# Un_51_V1_1.net
KiCad netlist of a schematic drawn in EAGLE
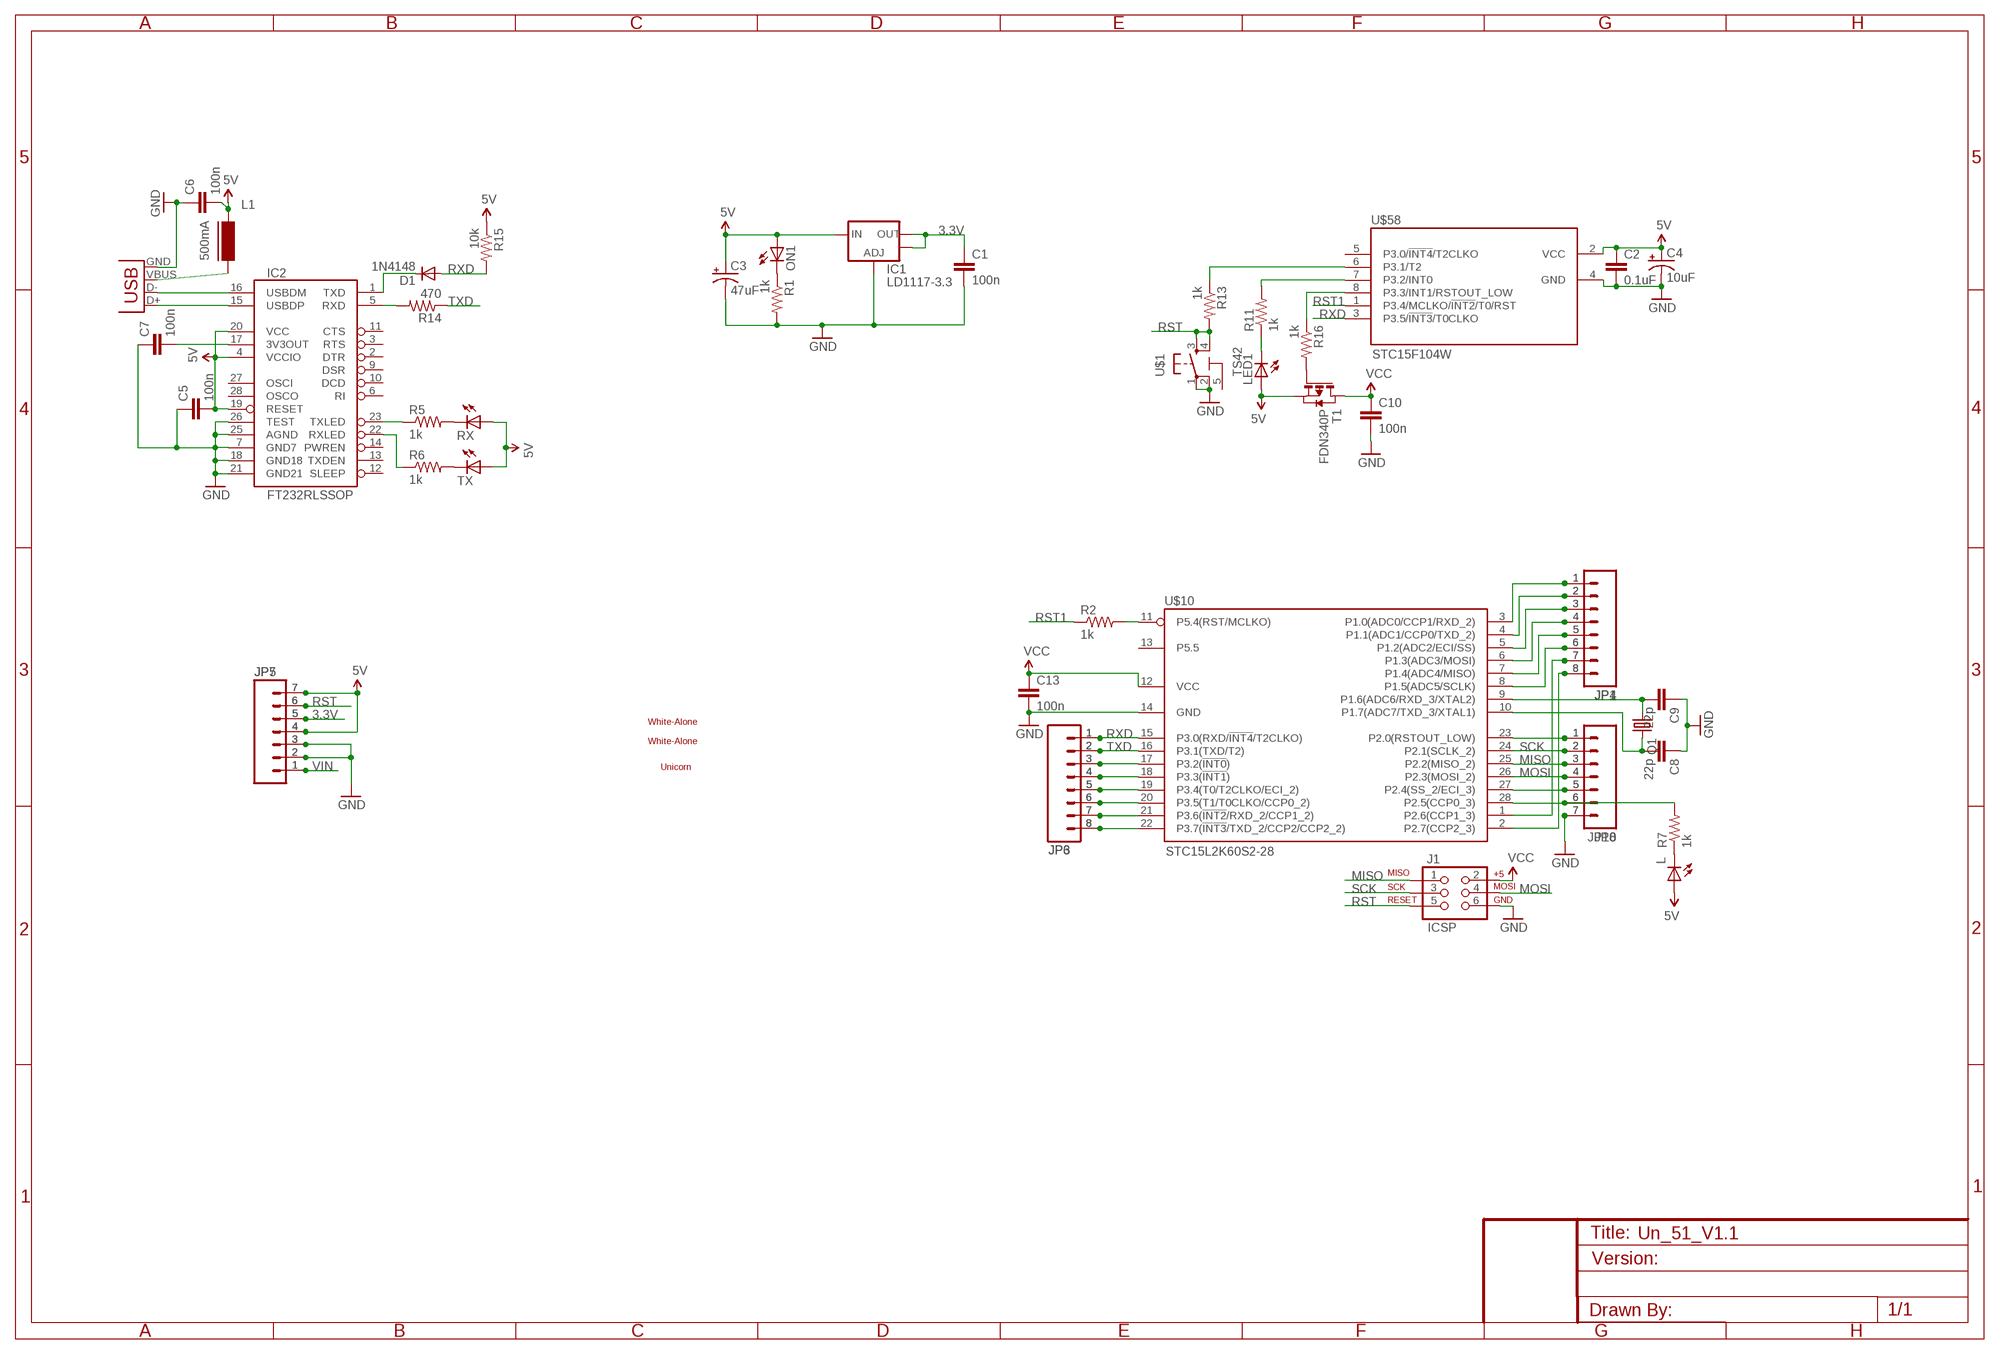
[diagram p0: schematic, sheet 1]

(export (version "E")
  (design (tool "Eeschema 10.0.6"))
  (components
    (comp (ref "C1")
      (value "100n")
      (footprint "eagle-import:0603-CAP")
      (libsource (lib "eagle-import") (part "2SparkFun_CAP0603-CAP"))
    )
    (comp (ref "C2")
      (value "0.1uF")
      (footprint "eagle-import:0603-CAP")
      (libsource (lib "eagle-import") (part "2SparkFun_CAP0603-CAP"))
    )
    (comp (ref "C3")
      (value "47uF")
      (footprint "eagle-import:PANASONIC_D")
      (libsource (lib "eagle-import") (part "CAP_POLD"))
    )
    (comp (ref "C4")
      (value "10uF")
      (footprint "eagle-import:EIA3216")
      (libsource (lib "eagle-import") (part "CAP_POL1206"))
    )
    (comp (ref "C5")
      (value "100n")
      (footprint "eagle-import:0603-CAP")
      (libsource (lib "eagle-import") (part "2SparkFun_CAP0603-CAP"))
    )
    (comp (ref "C6")
      (value "100n")
      (footprint "eagle-import:0603-CAP")
      (libsource (lib "eagle-import") (part "2SparkFun_CAP0603-CAP"))
    )
    (comp (ref "C7")
      (value "100n")
      (footprint "eagle-import:0603-CAP")
      (libsource (lib "eagle-import") (part "2SparkFun_CAP0603-CAP"))
    )
    (comp (ref "C8")
      (value "22p")
      (footprint "eagle-import:0603-CAP")
      (libsource (lib "eagle-import") (part "2SparkFun_CAP0603-CAP"))
    )
    (comp (ref "C9")
      (value "22p")
      (footprint "eagle-import:0603-CAP")
      (libsource (lib "eagle-import") (part "2SparkFun_CAP0603-CAP"))
    )
    (comp (ref "C10")
      (value "100n")
      (footprint "eagle-import:0603-CAP")
      (libsource (lib "eagle-import") (part "2SparkFun_CAP0603-CAP"))
    )
    (comp (ref "C13")
      (value "100n")
      (footprint "eagle-import:0603-CAP")
      (libsource (lib "eagle-import") (part "CAP0603-CAP"))
    )
    (comp (ref "D1")
      (value "1N4148")
      (footprint "eagle-import:SOD-323")
      (libsource (lib "eagle-import") (part "DIODESOD"))
    )
    (comp (ref "IC1")
      (value "LD1117-3.3")
      (footprint "eagle-import:SOT223")
      (libsource (lib "eagle-import") (part "V_REG_LM1117SOT223"))
    )
    (comp (ref "IC2")
      (value "FT232RLSSOP")
      (footprint "eagle-import:SSOP28DB")
      (libsource (lib "eagle-import") (part "FT232RLSSOP"))
    )
    (comp (ref "J1")
      (value "ICSP")
      (footprint "eagle-import:2X3")
      (libsource (lib "eagle-import") (part "AVR_SPI_PRG_6PTH"))
    )
    (comp (ref "JP1")
      (value "M081X08")
      (footprint "eagle-import:1X08")
      (libsource (lib "eagle-import") (part "M081X08"))
    )
    (comp (ref "JP3")
      (value "M08")
      (footprint "eagle-import:1X08")
      (libsource (lib "eagle-import") (part "M08"))
    )
    (comp (ref "JP4")
      (value "M081X08")
      (footprint "eagle-import:1X08")
      (libsource (lib "eagle-import") (part "M081X08"))
    )
    (comp (ref "JP5")
      (value "M07")
      (footprint "eagle-import:1X07")
      (libsource (lib "eagle-import") (part "M07"))
    )
    (comp (ref "JP6")
      (value "M08")
      (footprint "eagle-import:1X08")
      (libsource (lib "eagle-import") (part "M08"))
    )
    (comp (ref "JP7")
      (value "M07")
      (footprint "eagle-import:1X07")
      (libsource (lib "eagle-import") (part "M07"))
    )
    (comp (ref "JP8")
      (value "M07")
      (footprint "eagle-import:1X07")
      (libsource (lib "eagle-import") (part "M07"))
    )
    (comp (ref "JP10")
      (value "M07")
      (footprint "eagle-import:1X07")
      (libsource (lib "eagle-import") (part "M07"))
    )
    (comp (ref "L")
      (value "LED0805")
      (footprint "eagle-import:LED-0805")
      (libsource (lib "eagle-import") (part "LED0805"))
    )
    (comp (ref "L1")
      (value "500mA")
      (footprint "eagle-import:FB805")
      (libsource (lib "eagle-import") (part "FERRITE-0805"))
    )
    (comp (ref "LED1")
      (value "LED0805")
      (footprint "eagle-import:LED-0805")
      (libsource (lib "eagle-import") (part "2SparkFun_LED0805"))
    )
    (comp (ref "ON1")
      (value "LED0805")
      (footprint "eagle-import:LED-0805")
      (libsource (lib "eagle-import") (part "LED0805"))
    )
    (comp (ref "Q1")
      (value "CRYSTALHC49US")
      (footprint "eagle-import:HC49US")
      (libsource (lib "eagle-import") (part "CRYSTALHC49US"))
    )
    (comp (ref "R1")
      (value "1k")
      (footprint "eagle-import:0603-RES")
      (libsource (lib "eagle-import") (part "RESISTOR0603-RES"))
    )
    (comp (ref "R2")
      (value "1k")
      (footprint "eagle-import:0603-RES")
      (libsource (lib "eagle-import") (part "RESISTOR0603-RES"))
    )
    (comp (ref "R5")
      (value "1k")
      (footprint "eagle-import:0603-RES")
      (libsource (lib "eagle-import") (part "RESISTOR0603-RES"))
    )
    (comp (ref "R6")
      (value "1k")
      (footprint "eagle-import:0603-RES")
      (libsource (lib "eagle-import") (part "RESISTOR0603-RES"))
    )
    (comp (ref "R7")
      (value "1k")
      (footprint "eagle-import:0603-RES")
      (libsource (lib "eagle-import") (part "RESISTOR0603-RES"))
    )
    (comp (ref "R11")
      (value "1k")
      (footprint "eagle-import:0603-RES")
      (libsource (lib "eagle-import") (part "RESISTOR0603-RES"))
    )
    (comp (ref "R13")
      (value "1k")
      (footprint "eagle-import:0603-RES")
      (libsource (lib "eagle-import") (part "RESISTOR0603-RES"))
    )
    (comp (ref "R14")
      (value "470")
      (footprint "eagle-import:0603-RES")
      (libsource (lib "eagle-import") (part "RESISTOR0603-RES"))
    )
    (comp (ref "R15")
      (value "10k")
      (footprint "eagle-import:0603-RES")
      (libsource (lib "eagle-import") (part "RESISTOR0603-RES"))
    )
    (comp (ref "R16")
      (value "1k")
      (footprint "eagle-import:0603-RES")
      (libsource (lib "eagle-import") (part "RESISTOR0603-RES"))
    )
    (comp (ref "RX")
      (value "LED0805")
      (footprint "eagle-import:LED-0805")
      (libsource (lib "eagle-import") (part "LED0805"))
    )
    (comp (ref "T1")
      (value "FDN340P")
      (footprint "eagle-import:SOT-23")
      (libsource (lib "eagle-import") (part "PMOSSOT23"))
    )
    (comp (ref "TX")
      (value "LED0805")
      (footprint "eagle-import:LED-0805")
      (libsource (lib "eagle-import") (part "LED0805"))
    )
    (comp (ref "U$1")
      (value "TS42")
      (footprint "eagle-import:TS42")
      (libsource (lib "eagle-import") (part "TS42"))
    )
    (comp (ref "U$3")
      (value "UNICORN")
      (footprint "eagle-import:UNICORN_1")
      (libsource (lib "eagle-import") (part "UNICORN"))
    )
    (comp (ref "U$7")
      (value "WHITE-ALONE_0")
      (footprint "eagle-import:WHITE-ALONE_0")
      (libsource (lib "eagle-import") (part "WHITE-ALONE_0"))
    )
    (comp (ref "U$10")
      (value "STC15L2K60S2-28")
      (footprint "eagle-import:SO-28W")
      (libsource (lib "eagle-import") (part "STC15L2K60S2-28"))
    )
    (comp (ref "U$11")
      (value "WHITE-ALONE_0")
      (footprint "eagle-import:WHITE-ALONE_0")
      (libsource (lib "eagle-import") (part "WHITE-ALONE_0"))
    )
    (comp (ref "U$58")
      (value "STC15F104W")
      (footprint "eagle-import:SO08")
      (libsource (lib "eagle-import") (part "STC15F104W"))
    )
    (comp (ref "X1")
      (value "USBSMD")
      (footprint "eagle-import:USB-MINIB")
      (libsource (lib "eagle-import") (part "USBSMD"))
    )
  )
  (nets
    (net (code "1") (name "/3.3V") (class "Default")
      (node (ref "C1") (pin "1") (pinfunction "1_1") (pintype "passive"))
      (node (ref "IC1") (pin "2") (pinfunction "OUT_2") (pintype "output"))
      (node (ref "IC1") (pin "4") (pinfunction "OUT_4") (pintype "output"))
      (node (ref "JP5") (pin "5") (pinfunction "5_5") (pintype "passive"))
      (node (ref "JP7") (pin "5") (pinfunction "5_5") (pintype "passive"))
    )
    (net (code "2") (name "/MISO") (class "Default")
      (node (ref "J1") (pin "1") (pinfunction "1_1") (pintype "passive"))
      (node (ref "JP10") (pin "3") (pinfunction "3_3") (pintype "passive"))
      (node (ref "JP8") (pin "3") (pinfunction "3_3") (pintype "passive"))
      (node (ref "U$10") (pin "25") (pinfunction "P2.2(MISO_2)_25") (pintype "bidirectional"))
    )
    (net (code "3") (name "/MOSI") (class "Default")
      (node (ref "J1") (pin "4") (pinfunction "4_4") (pintype "passive"))
      (node (ref "JP10") (pin "4") (pinfunction "4_4") (pintype "passive"))
      (node (ref "JP8") (pin "4") (pinfunction "4_4") (pintype "passive"))
      (node (ref "U$10") (pin "26") (pinfunction "P2.3(MOSI_2)_26") (pintype "bidirectional"))
    )
    (net (code "4") (name "/RST") (class "Default")
      (node (ref "J1") (pin "5") (pinfunction "5_5") (pintype "passive"))
      (node (ref "JP5") (pin "6") (pinfunction "6_6") (pintype "passive"))
      (node (ref "JP7") (pin "6") (pinfunction "6_6") (pintype "passive"))
      (node (ref "R13") (pin "2") (pinfunction "2_2") (pintype "passive"))
      (node (ref "U$1") (pin "3") (pinfunction "3_3") (pintype "passive"))
      (node (ref "U$1") (pin "4") (pinfunction "4_4") (pintype "passive"))
    )
    (net (code "5") (name "/RST1") (class "Default")
      (node (ref "R2") (pin "1") (pinfunction "1_1") (pintype "passive"))
      (node (ref "U$58") (pin "1") (pinfunction "P3.4/MCLKO/~{INT2}/T0/RST_1") (pintype "bidirectional"))
    )
    (net (code "6") (name "/RXD") (class "Default")
      (node (ref "D1") (pin "2") (pinfunction "A_2") (pintype "passive"))
      (node (ref "JP3") (pin "1") (pinfunction "1_1") (pintype "passive"))
      (node (ref "JP6") (pin "1") (pinfunction "1_1") (pintype "passive"))
      (node (ref "R15") (pin "2") (pinfunction "2_2") (pintype "passive"))
      (node (ref "U$10") (pin "15") (pinfunction "P3.0(RXD/~{INT4}/T2CLKO)_15") (pintype "bidirectional"))
      (node (ref "U$58") (pin "3") (pinfunction "P3.5/~{INT3}/T0CLKO_3") (pintype "bidirectional"))
    )
    (net (code "7") (name "/SCK") (class "Default")
      (node (ref "J1") (pin "3") (pinfunction "3_3") (pintype "passive"))
      (node (ref "JP10") (pin "2") (pinfunction "2_2") (pintype "passive"))
      (node (ref "JP8") (pin "2") (pinfunction "2_2") (pintype "passive"))
      (node (ref "U$10") (pin "24") (pinfunction "P2.1(SCLK_2)_24") (pintype "bidirectional"))
    )
    (net (code "8") (name "/TXD") (class "Default")
      (node (ref "JP3") (pin "2") (pinfunction "2_2") (pintype "passive"))
      (node (ref "JP6") (pin "2") (pinfunction "2_2") (pintype "passive"))
      (node (ref "R14") (pin "1") (pinfunction "1_1") (pintype "passive"))
      (node (ref "U$10") (pin "16") (pinfunction "P3.1(TXD/T2)_16") (pintype "bidirectional"))
    )
    (net (code "9") (name "/VIN") (class "Default")
      (node (ref "JP5") (pin "1") (pinfunction "1_1") (pintype "passive"))
      (node (ref "JP7") (pin "1") (pinfunction "1_1") (pintype "passive"))
    )
    (net (code "10") (name "5V") (class "Default")
      (node (ref "C2") (pin "1") (pinfunction "1_1") (pintype "passive"))
      (node (ref "C3") (pin "+") (pinfunction "+_+") (pintype "passive"))
      (node (ref "C4") (pin "A") (pinfunction "+_A") (pintype "passive"))
      (node (ref "C5") (pin "2") (pinfunction "2_2") (pintype "passive"))
      (node (ref "C6") (pin "2") (pinfunction "2_2") (pintype "passive"))
      (node (ref "IC1") (pin "3") (pinfunction "IN_3") (pintype "input"))
      (node (ref "IC2") (pin "19") (pinfunction "RESET_19") (pintype "input"))
      (node (ref "IC2") (pin "20") (pinfunction "VCC_20") (pintype "power_in"))
      (node (ref "IC2") (pin "4") (pinfunction "VCCIO_4") (pintype "power_in"))
      (node (ref "JP5") (pin "4") (pinfunction "4_4") (pintype "passive"))
      (node (ref "JP5") (pin "7") (pinfunction "7_7") (pintype "passive"))
      (node (ref "JP7") (pin "4") (pinfunction "4_4") (pintype "passive"))
      (node (ref "JP7") (pin "7") (pinfunction "7_7") (pintype "passive"))
      (node (ref "L") (pin "1") (pinfunction "A_1") (pintype "passive"))
      (node (ref "L1") (pin "1") (pinfunction "1_1") (pintype "passive"))
      (node (ref "LED1") (pin "1") (pinfunction "A_1") (pintype "passive"))
      (node (ref "ON1") (pin "1") (pinfunction "A_1") (pintype "passive"))
      (node (ref "R15") (pin "1") (pinfunction "1_1") (pintype "passive"))
      (node (ref "RX") (pin "1") (pinfunction "A_1") (pintype "passive"))
      (node (ref "T1") (pin "2") (pinfunction "S_2") (pintype "passive"))
      (node (ref "TX") (pin "1") (pinfunction "A_1") (pintype "passive"))
      (node (ref "U$58") (pin "2") (pinfunction "VCC_2") (pintype "bidirectional"))
    )
    (net (code "11") (name "GND") (class "Default")
      (node (ref "C1") (pin "2") (pinfunction "2_2") (pintype "passive"))
      (node (ref "C10") (pin "2") (pinfunction "2_2") (pintype "passive"))
      (node (ref "C13") (pin "2") (pinfunction "2_2") (pintype "passive"))
      (node (ref "C2") (pin "2") (pinfunction "2_2") (pintype "passive"))
      (node (ref "C3") (pin "-") (pinfunction "-_-") (pintype "passive"))
      (node (ref "C4") (pin "C") (pinfunction "-_C") (pintype "passive"))
      (node (ref "C5") (pin "1") (pinfunction "1_1") (pintype "passive"))
      (node (ref "C6") (pin "1") (pinfunction "1_1") (pintype "passive"))
      (node (ref "C7") (pin "1") (pinfunction "1_1") (pintype "passive"))
      (node (ref "C8") (pin "1") (pinfunction "1_1") (pintype "passive"))
      (node (ref "C9") (pin "1") (pinfunction "1_1") (pintype "passive"))
      (node (ref "IC1") (pin "1") (pinfunction "ADJ_1") (pintype "input"))
      (node (ref "IC2") (pin "18") (pinfunction "GND18_18") (pintype "power_in"))
      (node (ref "IC2") (pin "21") (pinfunction "GND21_21") (pintype "power_in"))
      (node (ref "IC2") (pin "25") (pinfunction "AGND_25") (pintype "power_in"))
      (node (ref "IC2") (pin "26") (pinfunction "TEST_26") (pintype "input"))
      (node (ref "IC2") (pin "7") (pinfunction "GND7_7") (pintype "power_in"))
      (node (ref "J1") (pin "6") (pinfunction "6_6") (pintype "passive"))
      (node (ref "JP10") (pin "7") (pinfunction "7_7") (pintype "passive"))
      (node (ref "JP5") (pin "2") (pinfunction "2_2") (pintype "passive"))
      (node (ref "JP5") (pin "3") (pinfunction "3_3") (pintype "passive"))
      (node (ref "JP7") (pin "2") (pinfunction "2_2") (pintype "passive"))
      (node (ref "JP7") (pin "3") (pinfunction "3_3") (pintype "passive"))
      (node (ref "JP8") (pin "7") (pinfunction "7_7") (pintype "passive"))
      (node (ref "R1") (pin "2") (pinfunction "2_2") (pintype "passive"))
      (node (ref "U$1") (pin "1") (pinfunction "1_1") (pintype "passive"))
      (node (ref "U$1") (pin "2") (pinfunction "2_2") (pintype "passive"))
      (node (ref "U$10") (pin "14") (pinfunction "GND_14") (pintype "bidirectional"))
      (node (ref "U$58") (pin "4") (pinfunction "GND_4") (pintype "bidirectional"))
      (node (ref "X1") (pin "GND") (pinfunction "GND_GND") (pintype "bidirectional"))
    )
    (net (code "12") (name "Net-(D1-C)") (class "Default")
      (node (ref "D1") (pin "1") (pinfunction "C_1") (pintype "passive"))
      (node (ref "IC2") (pin "1") (pinfunction "TXD_1") (pintype "output"))
    )
    (net (code "13") (name "Net-(IC2-3V3OUT)") (class "Default")
      (node (ref "C7") (pin "2") (pinfunction "2_2") (pintype "passive"))
      (node (ref "IC2") (pin "17") (pinfunction "3V3OUT_17") (pintype "output"))
    )
    (net (code "14") (name "Net-(IC2-RXD)") (class "Default")
      (node (ref "IC2") (pin "5") (pinfunction "RXD_5") (pintype "input"))
      (node (ref "R14") (pin "2") (pinfunction "2_2") (pintype "passive"))
    )
    (net (code "15") (name "Net-(IC2-RXLED)") (class "Default")
      (node (ref "IC2") (pin "22") (pinfunction "RXLED_22") (pintype "input"))
      (node (ref "R6") (pin "1") (pinfunction "1_1") (pintype "passive"))
    )
    (net (code "16") (name "Net-(IC2-TXLED)") (class "Default")
      (node (ref "IC2") (pin "23") (pinfunction "TXLED_23") (pintype "input"))
      (node (ref "R5") (pin "1") (pinfunction "1_1") (pintype "passive"))
    )
    (net (code "17") (name "Net-(IC2-USBDM)") (class "Default")
      (node (ref "IC2") (pin "16") (pinfunction "USBDM_16") (pintype "bidirectional"))
      (node (ref "X1") (pin "D-") (pinfunction "D-_D-") (pintype "bidirectional"))
    )
    (net (code "18") (name "Net-(IC2-USBDP)") (class "Default")
      (node (ref "IC2") (pin "15") (pinfunction "USBDP_15") (pintype "bidirectional"))
      (node (ref "X1") (pin "D+") (pinfunction "D+_D+") (pintype "bidirectional"))
    )
    (net (code "19") (name "Net-(L-C)") (class "Default")
      (node (ref "L") (pin "2") (pinfunction "C_2") (pintype "passive"))
      (node (ref "R7") (pin "1") (pinfunction "1_1") (pintype "passive"))
    )
    (net (code "20") (name "Net-(L1-Pad2)") (class "Default")
      (node (ref "L1") (pin "2") (pinfunction "2_2") (pintype "passive"))
      (node (ref "X1") (pin "VBUS") (pinfunction "VBUS_VBUS") (pintype "bidirectional"))
    )
    (net (code "21") (name "Net-(LED1-C)") (class "Default")
      (node (ref "LED1") (pin "2") (pinfunction "C_2") (pintype "passive"))
      (node (ref "R11") (pin "1") (pinfunction "1_1") (pintype "passive"))
    )
    (net (code "22") (name "Net-(ON1-C)") (class "Default")
      (node (ref "ON1") (pin "2") (pinfunction "C_2") (pintype "passive"))
      (node (ref "R1") (pin "1") (pinfunction "1_1") (pintype "passive"))
    )
    (net (code "23") (name "Net-(RX-C)") (class "Default")
      (node (ref "R5") (pin "2") (pinfunction "2_2") (pintype "passive"))
      (node (ref "RX") (pin "2") (pinfunction "C_2") (pintype "passive"))
    )
    (net (code "24") (name "Net-(T1-G)") (class "Default")
      (node (ref "R16") (pin "2") (pinfunction "2_2") (pintype "passive"))
      (node (ref "T1") (pin "3") (pinfunction "G_3") (pintype "passive"))
    )
    (net (code "25") (name "Net-(TX-C)") (class "Default")
      (node (ref "R6") (pin "2") (pinfunction "2_2") (pintype "passive"))
      (node (ref "TX") (pin "2") (pinfunction "C_2") (pintype "passive"))
    )
    (net (code "26") (name "Net-(U$10-P1.0(ADC0{slash}CCP1{slash}RXD_2))") (class "Default")
      (node (ref "JP1") (pin "1") (pinfunction "1_1") (pintype "passive"))
      (node (ref "JP4") (pin "1") (pinfunction "1_1") (pintype "passive"))
      (node (ref "U$10") (pin "3") (pinfunction "P1.0(ADC0/CCP1/RXD_2)_3") (pintype "bidirectional"))
    )
    (net (code "27") (name "Net-(U$10-P1.1(ADC1{slash}CCP0{slash}TXD_2))") (class "Default")
      (node (ref "JP1") (pin "2") (pinfunction "2_2") (pintype "passive"))
      (node (ref "JP4") (pin "2") (pinfunction "2_2") (pintype "passive"))
      (node (ref "U$10") (pin "4") (pinfunction "P1.1(ADC1/CCP0/TXD_2)_4") (pintype "bidirectional"))
    )
    (net (code "28") (name "Net-(U$10-P1.2(ADC2{slash}ECI{slash}SS))") (class "Default")
      (node (ref "JP1") (pin "3") (pinfunction "3_3") (pintype "passive"))
      (node (ref "JP4") (pin "3") (pinfunction "3_3") (pintype "passive"))
      (node (ref "U$10") (pin "5") (pinfunction "P1.2(ADC2/ECI/SS)_5") (pintype "bidirectional"))
    )
    (net (code "29") (name "Net-(U$10-P1.3(ADC3{slash}MOSI))") (class "Default")
      (node (ref "JP1") (pin "4") (pinfunction "4_4") (pintype "passive"))
      (node (ref "JP4") (pin "4") (pinfunction "4_4") (pintype "passive"))
      (node (ref "U$10") (pin "6") (pinfunction "P1.3(ADC3/MOSI)_6") (pintype "bidirectional"))
    )
    (net (code "30") (name "Net-(U$10-P1.4(ADC4{slash}MISO))") (class "Default")
      (node (ref "JP1") (pin "5") (pinfunction "5_5") (pintype "passive"))
      (node (ref "JP4") (pin "5") (pinfunction "5_5") (pintype "passive"))
      (node (ref "U$10") (pin "7") (pinfunction "P1.4(ADC4/MISO)_7") (pintype "bidirectional"))
    )
    (net (code "31") (name "Net-(U$10-P1.5(ADC5{slash}SCLK))") (class "Default")
      (node (ref "JP1") (pin "6") (pinfunction "6_6") (pintype "passive"))
      (node (ref "JP4") (pin "6") (pinfunction "6_6") (pintype "passive"))
      (node (ref "U$10") (pin "8") (pinfunction "P1.5(ADC5/SCLK)_8") (pintype "bidirectional"))
    )
    (net (code "32") (name "Net-(U$10-P1.6(ADC6{slash}RXD_3{slash}XTAL2))") (class "Default")
      (node (ref "C9") (pin "2") (pinfunction "2_2") (pintype "passive"))
      (node (ref "Q1") (pin "1") (pinfunction "1_1") (pintype "passive"))
      (node (ref "U$10") (pin "9") (pinfunction "P1.6(ADC6/RXD_3/XTAL2)_9") (pintype "bidirectional"))
    )
    (net (code "33") (name "Net-(U$10-P1.7(ADC7{slash}TXD_3{slash}XTAL1))") (class "Default")
      (node (ref "C8") (pin "2") (pinfunction "2_2") (pintype "passive"))
      (node (ref "Q1") (pin "2") (pinfunction "2_2") (pintype "passive"))
      (node (ref "U$10") (pin "10") (pinfunction "P1.7(ADC7/TXD_3/XTAL1)_10") (pintype "bidirectional"))
    )
    (net (code "34") (name "Net-(U$10-P2.0(RSTOUT_LOW))") (class "Default")
      (node (ref "JP10") (pin "1") (pinfunction "1_1") (pintype "passive"))
      (node (ref "JP8") (pin "1") (pinfunction "1_1") (pintype "passive"))
      (node (ref "U$10") (pin "23") (pinfunction "P2.0(RSTOUT_LOW)_23") (pintype "bidirectional"))
    )
    (net (code "35") (name "Net-(U$10-P2.4(SS_2{slash}ECI_3))") (class "Default")
      (node (ref "JP10") (pin "5") (pinfunction "5_5") (pintype "passive"))
      (node (ref "JP8") (pin "5") (pinfunction "5_5") (pintype "passive"))
      (node (ref "U$10") (pin "27") (pinfunction "P2.4(SS_2/ECI_3)_27") (pintype "bidirectional"))
    )
    (net (code "36") (name "Net-(U$10-P2.5(CCP0_3))") (class "Default")
      (node (ref "JP10") (pin "6") (pinfunction "6_6") (pintype "passive"))
      (node (ref "JP8") (pin "6") (pinfunction "6_6") (pintype "passive"))
      (node (ref "R7") (pin "2") (pinfunction "2_2") (pintype "passive"))
      (node (ref "U$10") (pin "28") (pinfunction "P2.5(CCP0_3)_28") (pintype "bidirectional"))
    )
    (net (code "37") (name "Net-(U$10-P2.6(CCP1_3))") (class "Default")
      (node (ref "JP1") (pin "7") (pinfunction "7_7") (pintype "passive"))
      (node (ref "JP4") (pin "7") (pinfunction "7_7") (pintype "passive"))
      (node (ref "U$10") (pin "1") (pinfunction "P2.6(CCP1_3)_1") (pintype "bidirectional"))
    )
    (net (code "38") (name "Net-(U$10-P2.7(CCP2_3))") (class "Default")
      (node (ref "JP1") (pin "8") (pinfunction "8_8") (pintype "passive"))
      (node (ref "JP4") (pin "8") (pinfunction "8_8") (pintype "passive"))
      (node (ref "U$10") (pin "2") (pinfunction "P2.7(CCP2_3)_2") (pintype "bidirectional"))
    )
    (net (code "39") (name "Net-(U$10-P3.2(~{INT0}))") (class "Default")
      (node (ref "JP3") (pin "3") (pinfunction "3_3") (pintype "passive"))
      (node (ref "JP6") (pin "3") (pinfunction "3_3") (pintype "passive"))
      (node (ref "U$10") (pin "17") (pinfunction "P3.2(~{INT0})_17") (pintype "bidirectional"))
    )
    (net (code "40") (name "Net-(U$10-P3.3(~{INT1}))") (class "Default")
      (node (ref "JP3") (pin "4") (pinfunction "4_4") (pintype "passive"))
      (node (ref "JP6") (pin "4") (pinfunction "4_4") (pintype "passive"))
      (node (ref "U$10") (pin "18") (pinfunction "P3.3(~{INT1})_18") (pintype "bidirectional"))
    )
    (net (code "41") (name "Net-(U$10-P3.4(T0{slash}T2CLKO{slash}ECI_2))") (class "Default")
      (node (ref "JP3") (pin "5") (pinfunction "5_5") (pintype "passive"))
      (node (ref "JP6") (pin "5") (pinfunction "5_5") (pintype "passive"))
      (node (ref "U$10") (pin "19") (pinfunction "P3.4(T0/T2CLKO/ECI_2)_19") (pintype "bidirectional"))
    )
    (net (code "42") (name "Net-(U$10-P3.5(T1{slash}T0CLKO{slash}CCP0_2))") (class "Default")
      (node (ref "JP3") (pin "6") (pinfunction "6_6") (pintype "passive"))
      (node (ref "JP6") (pin "6") (pinfunction "6_6") (pintype "passive"))
      (node (ref "U$10") (pin "20") (pinfunction "P3.5(T1/T0CLKO/CCP0_2)_20") (pintype "bidirectional"))
    )
    (net (code "43") (name "Net-(U$10-P3.6(~{INT2}{slash}RXD_2{slash}CCP1_2))") (class "Default")
      (node (ref "JP3") (pin "7") (pinfunction "7_7") (pintype "passive"))
      (node (ref "JP6") (pin "7") (pinfunction "7_7") (pintype "passive"))
      (node (ref "U$10") (pin "21") (pinfunction "P3.6(~{INT2}/RXD_2/CCP1_2)_21") (pintype "bidirectional"))
    )
    (net (code "44") (name "Net-(U$10-P3.7(~{INT3}{slash}TXD_2{slash}CCP2{slash}CCP2_2))") (class "Default")
      (node (ref "JP3") (pin "8") (pinfunction "8_8") (pintype "passive"))
      (node (ref "JP6") (pin "8") (pinfunction "8_8") (pintype "passive"))
      (node (ref "U$10") (pin "22") (pinfunction "P3.7(~{INT3}/TXD_2/CCP2/CCP2_2)_22") (pintype "bidirectional"))
    )
    (net (code "45") (name "Net-(U$10-P5.4(RST{slash}MCLKO))") (class "Default")
      (node (ref "R2") (pin "2") (pinfunction "2_2") (pintype "passive"))
      (node (ref "U$10") (pin "11") (pinfunction "P5.4(RST/MCLKO)_11") (pintype "bidirectional"))
    )
    (net (code "46") (name "Net-(U$58-P3.1{slash}T2)") (class "Default")
      (node (ref "R13") (pin "1") (pinfunction "1_1") (pintype "passive"))
      (node (ref "U$58") (pin "6") (pinfunction "P3.1/T2_6") (pintype "bidirectional"))
    )
    (net (code "47") (name "Net-(U$58-P3.2{slash}INT0)") (class "Default")
      (node (ref "R11") (pin "2") (pinfunction "2_2") (pintype "passive"))
      (node (ref "U$58") (pin "7") (pinfunction "P3.2/INT0_7") (pintype "bidirectional"))
    )
    (net (code "48") (name "Net-(U$58-P3.3{slash}INT1{slash}RSTOUT_LOW)") (class "Default")
      (node (ref "R16") (pin "1") (pinfunction "1_1") (pintype "passive"))
      (node (ref "U$58") (pin "8") (pinfunction "P3.3/INT1/RSTOUT_LOW_8") (pintype "bidirectional"))
    )
    (net (code "49") (name "VCC") (class "Default")
      (node (ref "C10") (pin "1") (pinfunction "1_1") (pintype "passive"))
      (node (ref "C13") (pin "1") (pinfunction "1_1") (pintype "passive"))
      (node (ref "J1") (pin "2") (pinfunction "2_2") (pintype "passive"))
      (node (ref "T1") (pin "1") (pinfunction "D_1") (pintype "passive"))
      (node (ref "U$10") (pin "12") (pinfunction "VCC_12") (pintype "bidirectional"))
    )
    (net (code "50") (name "unconnected-(IC2-CTS-Pad11)") (class "Default")
      (node (ref "IC2") (pin "11") (pinfunction "CTS_11") (pintype "input"))
    )
    (net (code "51") (name "unconnected-(IC2-DCD-Pad10)") (class "Default")
      (node (ref "IC2") (pin "10") (pinfunction "DCD_10") (pintype "input"))
    )
    (net (code "52") (name "unconnected-(IC2-DSR-Pad9)") (class "Default")
      (node (ref "IC2") (pin "9") (pinfunction "DSR_9") (pintype "input"))
    )
    (net (code "53") (name "unconnected-(IC2-DTR-Pad2)") (class "Default")
      (node (ref "IC2") (pin "2") (pinfunction "DTR_2") (pintype "output"))
    )
    (net (code "54") (name "unconnected-(IC2-OSCI-Pad27)") (class "Default")
      (node (ref "IC2") (pin "27") (pinfunction "OSCI_27") (pintype "input"))
    )
    (net (code "55") (name "unconnected-(IC2-OSCO-Pad28)") (class "Default")
      (node (ref "IC2") (pin "28") (pinfunction "OSCO_28") (pintype "output"))
    )
    (net (code "56") (name "unconnected-(IC2-PWREN-Pad14)") (class "Default")
      (node (ref "IC2") (pin "14") (pinfunction "PWREN_14") (pintype "input"))
    )
    (net (code "57") (name "unconnected-(IC2-RI-Pad6)") (class "Default")
      (node (ref "IC2") (pin "6") (pinfunction "RI_6") (pintype "input"))
    )
    (net (code "58") (name "unconnected-(IC2-RTS-Pad3)") (class "Default")
      (node (ref "IC2") (pin "3") (pinfunction "RTS_3") (pintype "output"))
    )
    (net (code "59") (name "unconnected-(IC2-SLEEP-Pad12)") (class "Default")
      (node (ref "IC2") (pin "12") (pinfunction "SLEEP_12") (pintype "input"))
    )
    (net (code "60") (name "unconnected-(IC2-TXDEN-Pad13)") (class "Default")
      (node (ref "IC2") (pin "13") (pinfunction "TXDEN_13") (pintype "input"))
    )
    (net (code "61") (name "unconnected-(U$1-Pad5)") (class "Default")
      (node (ref "U$1") (pin "5") (pinfunction "5_5") (pintype "passive"))
    )
    (net (code "62") (name "unconnected-(U$10-P5.5-Pad13)") (class "Default")
      (node (ref "U$10") (pin "13") (pinfunction "P5.5_13") (pintype "bidirectional"))
    )
    (net (code "63") (name "unconnected-(U$58-P3.0{slash}~{INT4}{slash}T2CLKO-Pad5)") (class "Default")
      (node (ref "U$58") (pin "5") (pinfunction "P3.0/~{INT4}/T2CLKO_5") (pintype "bidirectional"))
    )
  )
)
